# BW0253_POWER.net
KiCad netlist of a schematic drawn in Altium Designer
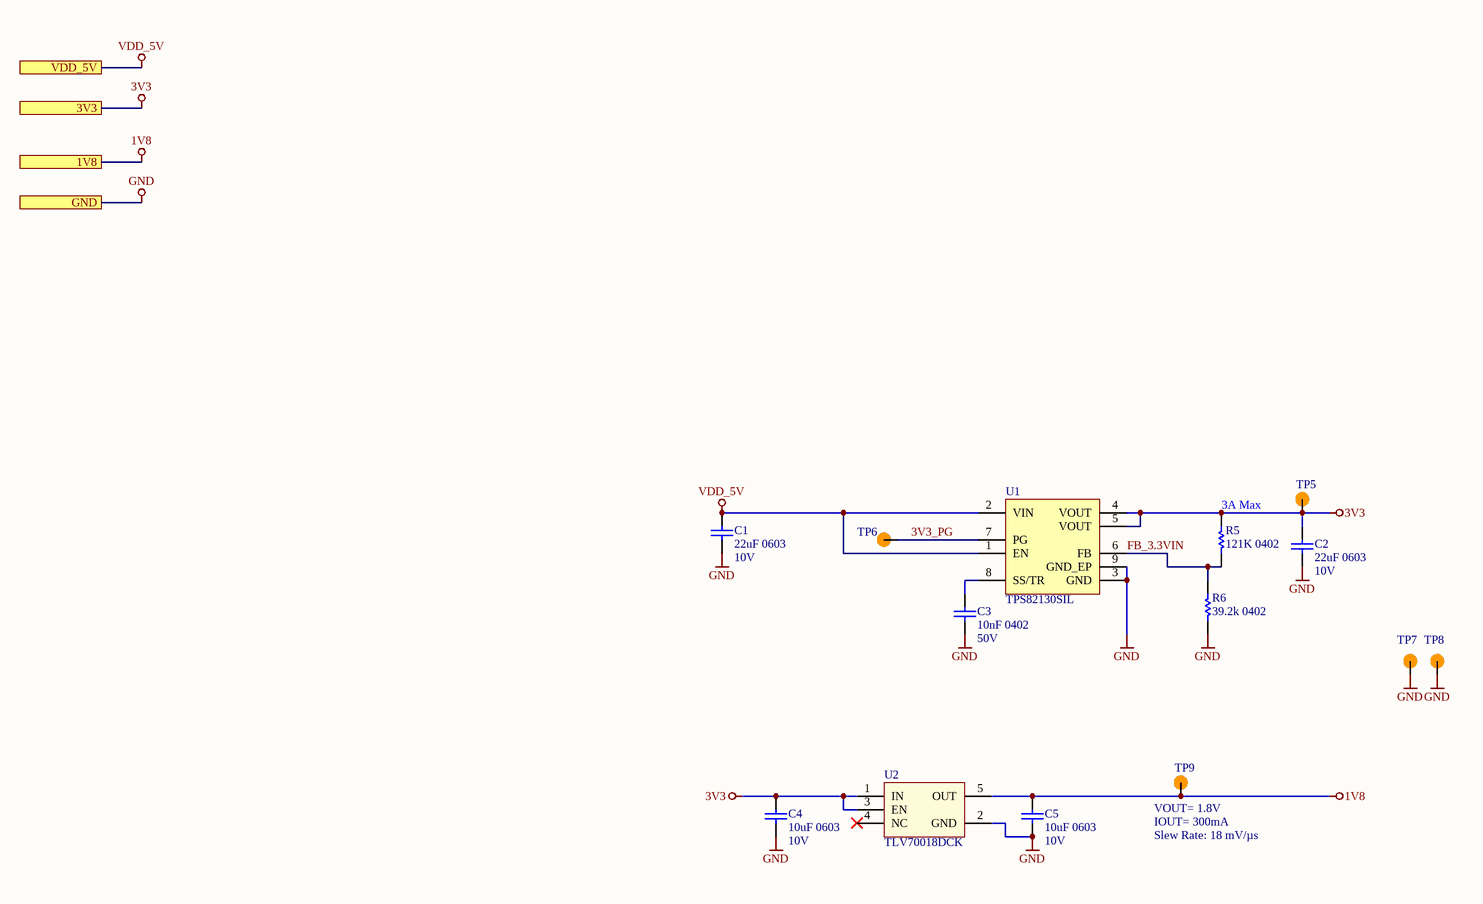
[diagram p0: BW0253_POWER.SchDoc]

(export (version "E")
  (design (tool "Eeschema 10.0.6"))
  (components
    (comp (ref "C1")
      (value "22uF 0603")
      (footprint "CAP_Altium_Vault_Generic:CAPC0603(1608)100_N")
      (description "CAP CER 22UF 10V X5R 0603 20%")
      (fields (field (name "TOLERANCE") "20%") (field (name "VOLTAGE RATING") "10V"))
      (libsource (lib "LuxonisMaster") (part "GRM188R61A226ME15D"))
    )
    (comp (ref "C2")
      (value "22uF 0603")
      (footprint "CAP_Altium_Vault_Generic:CAPC0603(1608)100_N")
      (description "CAP CER 22UF 10V X5R 0603 20%")
      (fields (field (name "TOLERANCE") "20%") (field (name "VOLTAGE RATING") "10V"))
      (libsource (lib "LuxonisMaster") (part "GRM188R61A226ME15D"))
    )
    (comp (ref "C3")
      (value "10nF 0402")
      (footprint "CAP_Altium_Vault_Generic:CAPC0402(1005)60_N")
      (description "CAP CER 10000PF 50V X7R 0402")
      (fields
        (field (name "TOLERANCE") "10%")
        (field (name "VOLTAGE") "25V")
        (field (name "VOLTAGE RATING") "50V")
      )
      (libsource (lib "LuxonisMaster") (part "GRM155R71H103KA88D"))
    )
    (comp (ref "C4")
      (value "10uF 0603")
      (footprint "CAP_Altium_Vault_Generic:CAPC0603(1608)100_N")
      (description "CAP CER 10UF 10V X5R 0603 20%")
      (fields (field (name "TOLERANCE") "20%") (field (name "VOLTAGE RATING") "10V"))
      (libsource (lib "LuxonisMaster") (part "GRM188R61A106ME69D"))
    )
    (comp (ref "C5")
      (value "10uF 0603")
      (footprint "CAP_Altium_Vault_Generic:CAPC0603(1608)100_N")
      (description "CAP CER 10UF 10V X5R 0603 20%")
      (fields (field (name "TOLERANCE") "20%") (field (name "VOLTAGE RATING") "10V"))
      (libsource (lib "LuxonisMaster") (part "GRM188R61A106ME69D"))
    )
    (comp (ref "R5")
      (value "121K 0402")
      (footprint "RES_Altium_Vault_Generic:RESC0402(1005)_N")
      (description "RES SMD 121K OHM 1% 1/16W 0402")
      (fields (field (name "TOLERANCE") "1%"))
      (libsource (lib "LuxonisMaster") (part "RC0402FR-07121KL"))
    )
    (comp (ref "R6")
      (value "39.2k 0402")
      (footprint "RES_Altium_Vault_Generic:RESC0402(1005)_N")
      (description "RES SMD 39.2K OHM 1% 1/16W 0402")
      (fields (field (name "TOLERANCE") "1%"))
      (libsource (lib "LuxonisMaster") (part "CRCW040239K2FKED"))
    )
    (comp (ref "TP5")
      (value "TP100_200_NS")
      (footprint "LuxonisMaster:TP100_200_NS")
      (libsource (lib "LuxonisMaster") (part "TEST_POINT"))
    )
    (comp (ref "TP6")
      (value "TP100_200_NS")
      (footprint "LuxonisMaster:TP100_200_NS")
      (libsource (lib "LuxonisMaster") (part "TEST_POINT"))
    )
    (comp (ref "TP7")
      (value "TP100_150_NS")
      (footprint "LuxonisMaster:TP100_150_NS")
      (libsource (lib "LuxonisMaster") (part "TEST_POINT"))
    )
    (comp (ref "TP8")
      (value "TP100_150_NS")
      (footprint "LuxonisMaster:TP100_150_NS")
      (libsource (lib "LuxonisMaster") (part "TEST_POINT"))
    )
    (comp (ref "TP9")
      (value "TP100_200_NS")
      (footprint "LuxonisMaster:TP100_200_NS")
      (libsource (lib "LuxonisMaster") (part "TEST_POINT"))
    )
    (comp (ref "U1")
      (value "TPS82130SIL")
      (footprint "LuxonisMaster:TPS82130SIL")
      (description "DC DC CONVERTER 0.9-5V")
      (libsource (lib "LuxonisMaster") (part "TPS82130SIL"))
    )
    (comp (ref "U2")
      (value "TLV70018DCK")
      (footprint "LuxonisMaster:TLV70018DCK")
      (description "IC REG LINEAR 1.8V 200MA SC70-5 Linear Voltage Regulator IC  1 Output  200mA SC-70-5")
      (libsource (lib "LuxonisMaster") (part "TLV70018DCK"))
    )
  )
  (nets
    (net (code "1") (name "/3V3_PG") (class "Default")
      (node (ref "TP6") (pin "1") (pintype "passive"))
      (node (ref "U1") (pin "7") (pinfunction "PG_7") (pintype "passive"))
    )
    (net (code "2") (name "/FB_3.3VIN") (class "Default")
      (node (ref "R5") (pin "2") (pinfunction "2_2") (pintype "passive"))
      (node (ref "R6") (pin "1") (pinfunction "1_1") (pintype "passive"))
      (node (ref "U1") (pin "6") (pinfunction "FB_6") (pintype "passive"))
    )
    (net (code "3") (name "1V8") (class "Default")
      (node (ref "C5") (pin "2") (pinfunction "2_2") (pintype "passive"))
      (node (ref "TP9") (pin "1") (pintype "passive"))
      (node (ref "U2") (pin "5") (pinfunction "OUT_5") (pintype "passive"))
    )
    (net (code "4") (name "3V3") (class "Default")
      (node (ref "C2") (pin "1") (pinfunction "1_1") (pintype "passive"))
      (node (ref "C4") (pin "2") (pinfunction "2_2") (pintype "passive"))
      (node (ref "R5") (pin "1") (pinfunction "1_1") (pintype "passive"))
      (node (ref "TP5") (pin "1") (pintype "passive"))
      (node (ref "U1") (pin "4") (pinfunction "VOUT_4") (pintype "passive"))
      (node (ref "U1") (pin "5") (pinfunction "VOUT_5") (pintype "passive"))
      (node (ref "U2") (pin "1") (pinfunction "IN_1") (pintype "passive"))
      (node (ref "U2") (pin "3") (pinfunction "EN_3") (pintype "passive"))
    )
    (net (code "5") (name "GND") (class "Default")
      (node (ref "C1") (pin "1") (pinfunction "1_1") (pintype "passive"))
      (node (ref "C2") (pin "2") (pinfunction "2_2") (pintype "passive"))
      (node (ref "C3") (pin "1") (pinfunction "1_1") (pintype "passive"))
      (node (ref "C4") (pin "1") (pinfunction "1_1") (pintype "passive"))
      (node (ref "C5") (pin "1") (pinfunction "1_1") (pintype "passive"))
      (node (ref "R6") (pin "2") (pinfunction "2_2") (pintype "passive"))
      (node (ref "TP7") (pin "1") (pintype "passive"))
      (node (ref "TP8") (pin "1") (pintype "passive"))
      (node (ref "U1") (pin "3") (pinfunction "GND_3") (pintype "passive"))
      (node (ref "U1") (pin "9") (pinfunction "GND_EP_9") (pintype "passive"))
      (node (ref "U2") (pin "2") (pinfunction "GND_2") (pintype "passive"))
    )
    (net (code "6") (name "Net-(U1-SS{slash}TR)") (class "Default")
      (node (ref "C3") (pin "2") (pinfunction "2_2") (pintype "passive"))
      (node (ref "U1") (pin "8") (pinfunction "SS/TR_8") (pintype "passive"))
    )
    (net (code "7") (name "VDD_5V") (class "Default")
      (node (ref "C1") (pin "2") (pinfunction "2_2") (pintype "passive"))
      (node (ref "U1") (pin "1") (pinfunction "EN_1") (pintype "passive"))
      (node (ref "U1") (pin "2") (pinfunction "VIN_2") (pintype "passive"))
    )
    (net (code "8") (name "unconnected-(U2-NC-Pad4)") (class "Default")
      (node (ref "U2") (pin "4") (pinfunction "NC_4") (pintype "passive+no_connect"))
    )
  )
)
